# routev3_3.net
KiCad netlist of a schematic drawn in EAGLE
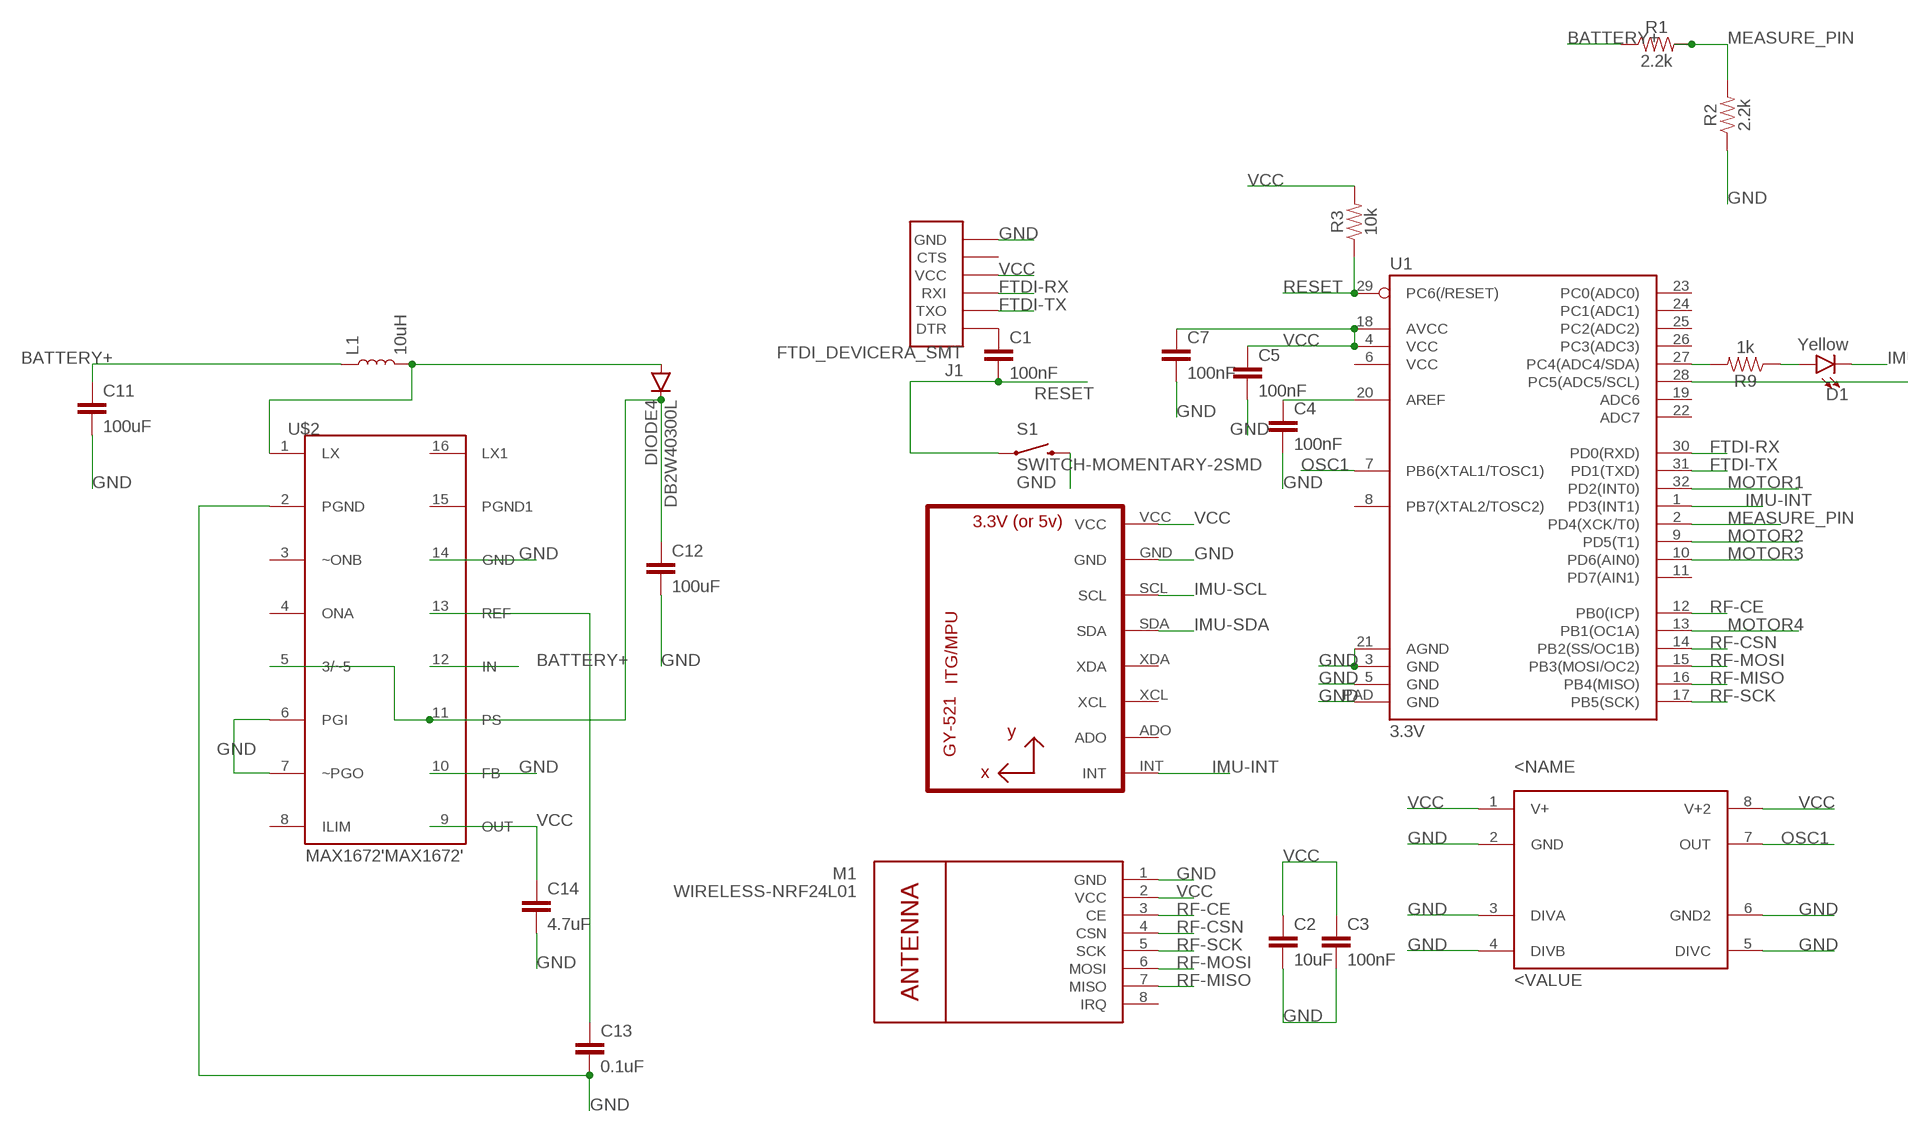
[diagram p0: schematic, sheet 1, part 1 of 2]
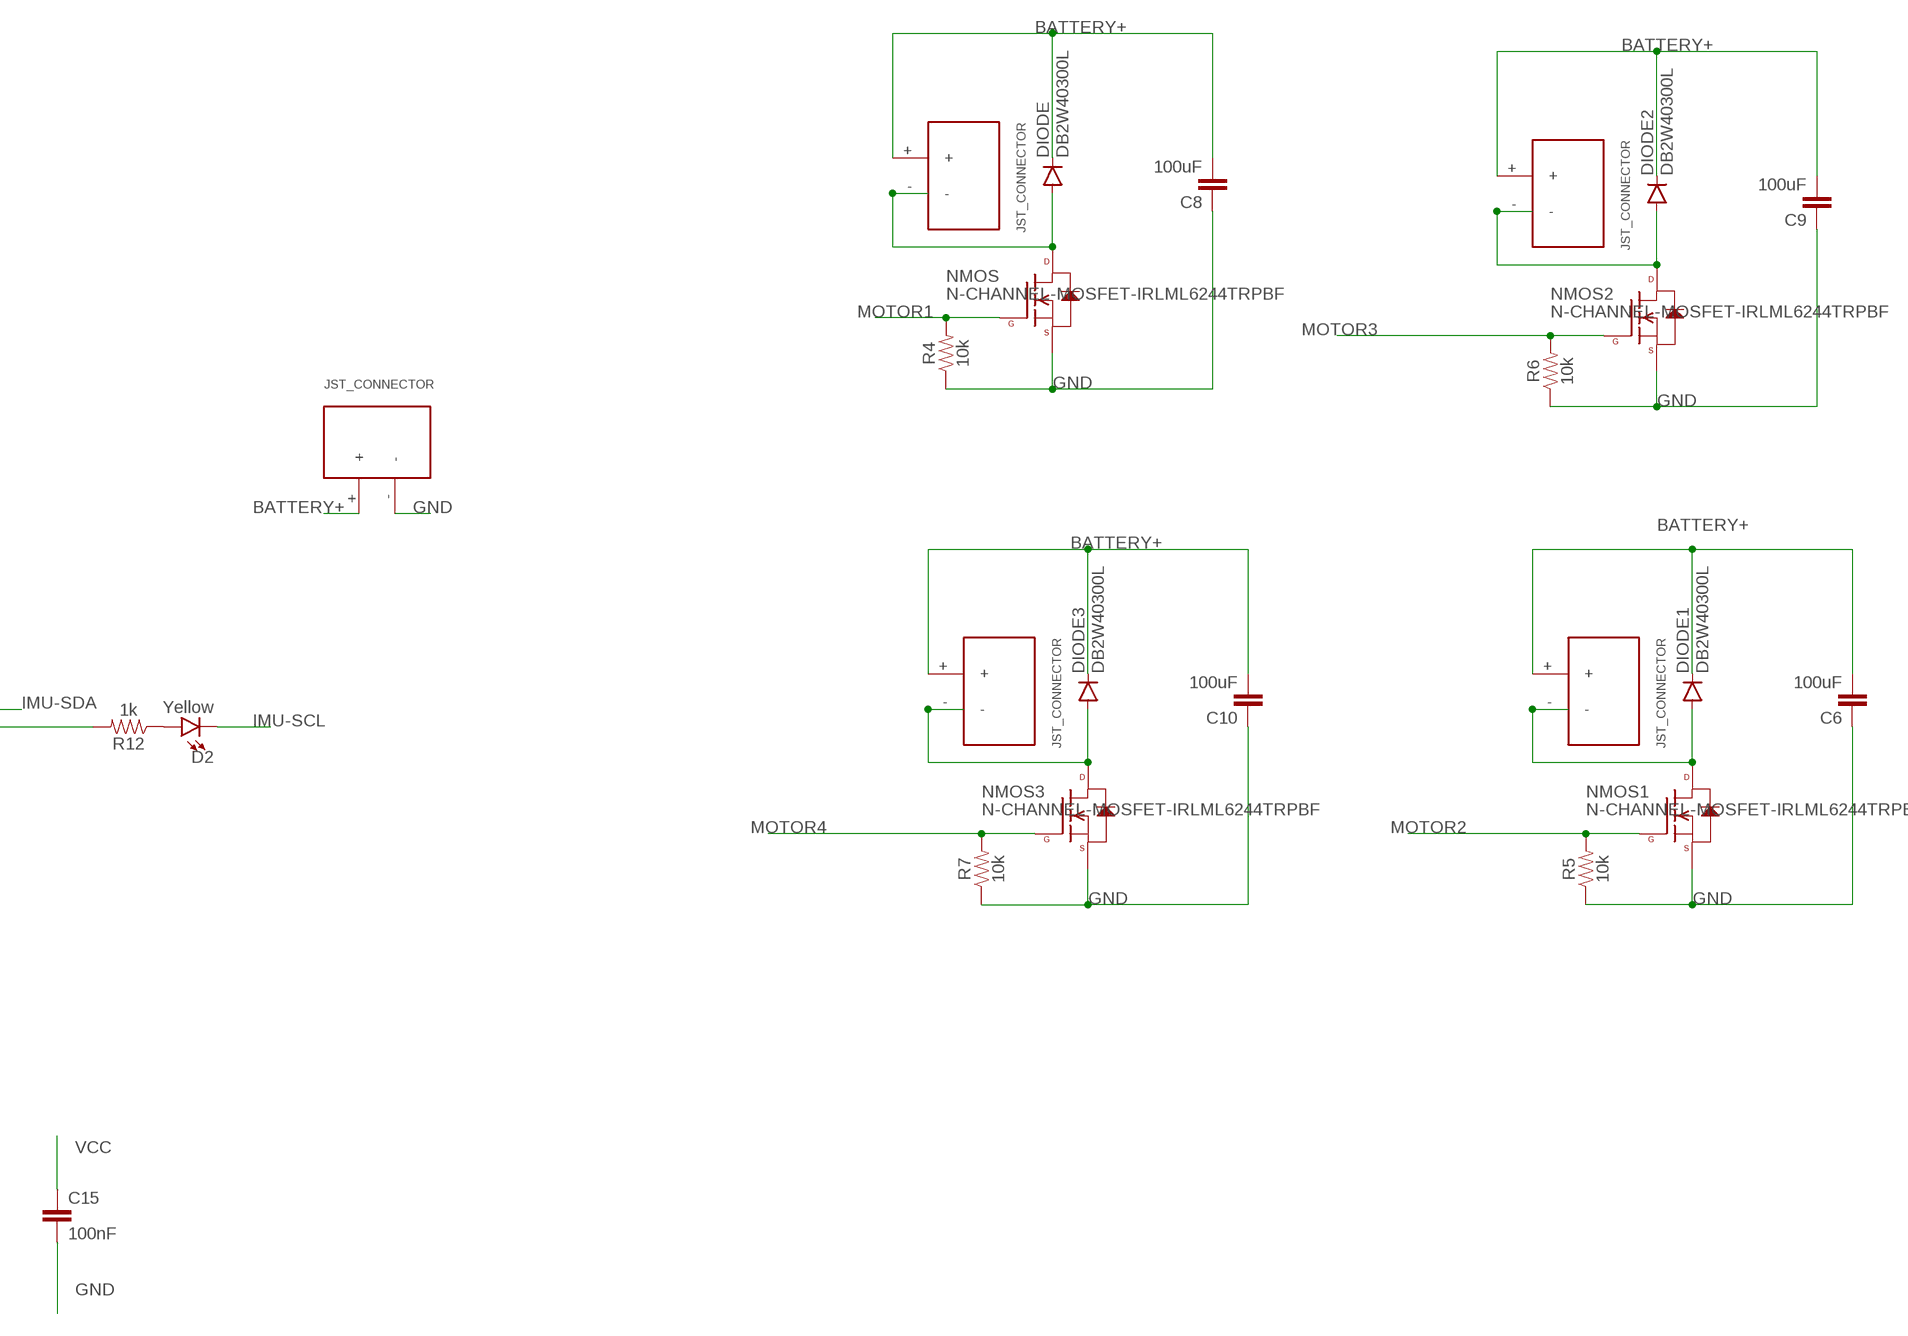
[diagram p1: schematic, sheet 1, part 2 of 2]

(export (version "E")
  (design (tool "Eeschema 10.0.6"))
  (components
    (comp (ref "C1")
      (value "100nF")
      (footprint "eagle-import:0603-CAP")
      (libsource (lib "eagle-import") (part "0.1UF-25V(+80/-20%)(0603)"))
    )
    (comp (ref "C2")
      (value "10uF")
      (footprint "eagle-import:0603-CAP")
      (libsource (lib "eagle-import") (part "CAP0603-CAP"))
    )
    (comp (ref "C3")
      (value "100nF")
      (footprint "eagle-import:0603-CAP")
      (libsource (lib "eagle-import") (part "CAP0603-CAP"))
    )
    (comp (ref "C4")
      (value "100nF")
      (footprint "eagle-import:0603-CAP")
      (libsource (lib "eagle-import") (part "CAP0603-CAP"))
    )
    (comp (ref "C5")
      (value "100nF")
      (footprint "eagle-import:0603-CAP")
      (libsource (lib "eagle-import") (part "CAP0603-CAP"))
    )
    (comp (ref "C6")
      (value "100uF")
      (footprint "eagle-import:0603-CAP")
      (libsource (lib "eagle-import") (part "CAP0603-CAP"))
    )
    (comp (ref "C7")
      (value "100nF")
      (footprint "eagle-import:0603-CAP")
      (libsource (lib "eagle-import") (part "CAP0603-CAP"))
    )
    (comp (ref "C8")
      (value "100uF")
      (footprint "eagle-import:0603-CAP")
      (libsource (lib "eagle-import") (part "CAP0603-CAP"))
    )
    (comp (ref "C9")
      (value "100uF")
      (footprint "eagle-import:0603-CAP")
      (libsource (lib "eagle-import") (part "CAP0603-CAP"))
    )
    (comp (ref "C10")
      (value "100uF")
      (footprint "eagle-import:0603-CAP")
      (libsource (lib "eagle-import") (part "CAP0603-CAP"))
    )
    (comp (ref "C11")
      (value "100uF")
      (footprint "eagle-import:0603-CAP")
      (libsource (lib "eagle-import") (part "CAP0603-CAP"))
    )
    (comp (ref "C12")
      (value "100uF")
      (footprint "eagle-import:0603-CAP")
      (libsource (lib "eagle-import") (part "CAP0603-CAP"))
    )
    (comp (ref "C13")
      (value "0.1uF")
      (footprint "eagle-import:0603-CAP")
      (libsource (lib "eagle-import") (part "CAP0603-CAP"))
    )
    (comp (ref "C14")
      (value "4.7uF")
      (footprint "eagle-import:0603-CAP")
      (libsource (lib "eagle-import") (part "CAP0603-CAP"))
    )
    (comp (ref "C15")
      (value "100nF")
      (footprint "eagle-import:0603-CAP")
      (libsource (lib "eagle-import") (part "0.1UF-25V(+80/-20%)(0603)"))
    )
    (comp (ref "D1")
      (value "Yellow")
      (footprint "eagle-import:LED-1206")
      (libsource (lib "eagle-import") (part "LED-YELLOWLILYPAD"))
    )
    (comp (ref "D2")
      (value "Yellow")
      (footprint "eagle-import:LED-1206")
      (libsource (lib "eagle-import") (part "LED-YELLOWLILYPAD"))
    )
    (comp (ref "DIODE")
      (value "DB2W40300L")
      (footprint "eagle-import:MINI2-F3-B")
      (libsource (lib "eagle-import") (part "DB2W40300L"))
    )
    (comp (ref "DIODE1")
      (value "DB2W40300L")
      (footprint "eagle-import:MINI2-F3-B")
      (libsource (lib "eagle-import") (part "DB2W40300L"))
    )
    (comp (ref "DIODE2")
      (value "DB2W40300L")
      (footprint "eagle-import:MINI2-F3-B")
      (libsource (lib "eagle-import") (part "DB2W40300L"))
    )
    (comp (ref "DIODE3")
      (value "DB2W40300L")
      (footprint "eagle-import:MINI2-F3-B")
      (libsource (lib "eagle-import") (part "DB2W40300L"))
    )
    (comp (ref "DIODE4")
      (value "DB2W40300L")
      (footprint "eagle-import:MINI2-F3-B")
      (libsource (lib "eagle-import") (part "DB2W40300L"))
    )
    (comp (ref "J1")
      (value "FTDI_DEVICERA_SMT")
      (footprint "eagle-import:FTDI_DEVICE_RA_SMT")
      (libsource (lib "eagle-import") (part "FTDI_DEVICERA_SMT"))
    )
    (comp (ref "L1")
      (value "10uH")
      (footprint "eagle-import:0603")
      (libsource (lib "eagle-import") (part "INDUCTOR-0603-33NH"))
    )
    (comp (ref "M1")
      (value "WIRELESS-NRF24L01")
      (footprint "eagle-import:WIRELESS-NRF24L01")
      (libsource (lib "eagle-import") (part "WIRELESS-NRF24L01"))
    )
    (comp (ref "MOTOR")
      (value "JST_CONNECTOR_FEMALE")
      (footprint "eagle-import:JST_CONNECTOR_FEMALE")
      (libsource (lib "eagle-import") (part "JST_CONNECTOR_FEMALE"))
    )
    (comp (ref "MOTOR1")
      (value "JST_CONNECTOR_FEMALE")
      (footprint "eagle-import:JST_CONNECTOR_FEMALE")
      (libsource (lib "eagle-import") (part "JST_CONNECTOR_FEMALE"))
    )
    (comp (ref "MOTOR2")
      (value "JST_CONNECTOR_FEMALE")
      (footprint "eagle-import:JST_CONNECTOR_FEMALE")
      (libsource (lib "eagle-import") (part "JST_CONNECTOR_FEMALE"))
    )
    (comp (ref "MOTOR3")
      (value "JST_CONNECTOR_FEMALE")
      (footprint "eagle-import:JST_CONNECTOR_FEMALE")
      (libsource (lib "eagle-import") (part "JST_CONNECTOR_FEMALE"))
    )
    (comp (ref "NMOS")
      (value "N-CHANNEL-MOSFET-IRLML6244TRPBF")
      (footprint "eagle-import:SOT23-3")
      (libsource (lib "eagle-import") (part "N-CHANNEL-MOSFET-IRLML6244TRPBF"))
    )
    (comp (ref "NMOS1")
      (value "N-CHANNEL-MOSFET-IRLML6244TRPBF")
      (footprint "eagle-import:SOT23-3")
      (libsource (lib "eagle-import") (part "N-CHANNEL-MOSFET-IRLML6244TRPBF"))
    )
    (comp (ref "NMOS2")
      (value "N-CHANNEL-MOSFET-IRLML6244TRPBF")
      (footprint "eagle-import:SOT23-3")
      (libsource (lib "eagle-import") (part "N-CHANNEL-MOSFET-IRLML6244TRPBF"))
    )
    (comp (ref "NMOS3")
      (value "N-CHANNEL-MOSFET-IRLML6244TRPBF")
      (footprint "eagle-import:SOT23-3")
      (libsource (lib "eagle-import") (part "N-CHANNEL-MOSFET-IRLML6244TRPBF"))
    )
    (comp (ref "R1")
      (value "2.2k")
      (footprint "eagle-import:0603")
      (libsource (lib "eagle-import") (part "2.2KOHM-0603-1/10W-1%"))
    )
    (comp (ref "R2")
      (value "2.2k")
      (footprint "eagle-import:0603")
      (libsource (lib "eagle-import") (part "2.2KOHM-0603-1/10W-1%"))
    )
    (comp (ref "R3")
      (value "10k")
      (footprint "eagle-import:0603")
      (libsource (lib "eagle-import") (part "2.2KOHM-0603-1/10W-1%"))
    )
    (comp (ref "R4")
      (value "10k")
      (footprint "eagle-import:0603")
      (libsource (lib "eagle-import") (part "2.2KOHM-0603-1/10W-1%"))
    )
    (comp (ref "R5")
      (value "10k")
      (footprint "eagle-import:0603")
      (libsource (lib "eagle-import") (part "2.2KOHM-0603-1/10W-1%"))
    )
    (comp (ref "R6")
      (value "10k")
      (footprint "eagle-import:0603")
      (libsource (lib "eagle-import") (part "2.2KOHM-0603-1/10W-1%"))
    )
    (comp (ref "R7")
      (value "10k")
      (footprint "eagle-import:0603")
      (libsource (lib "eagle-import") (part "2.2KOHM-0603-1/10W-1%"))
    )
    (comp (ref "R9")
      (value "1k")
      (footprint "eagle-import:0603")
      (libsource (lib "eagle-import") (part "2.2KOHM-0603-1/10W-1%"))
    )
    (comp (ref "R12")
      (value "1k")
      (footprint "eagle-import:0603")
      (libsource (lib "eagle-import") (part "2.2KOHM-0603-1/10W-1%"))
    )
    (comp (ref "S1")
      (value "SWITCH-MOMENTARY-2SMD")
      (footprint "eagle-import:TACTILE-SWITCH-SMD")
      (libsource (lib "eagle-import") (part "SWITCH-MOMENTARY-2SMD"))
    )
    (comp (ref "U$1")
      (value "JST_CONNECTOR_FEMALE")
      (footprint "eagle-import:JST_CONNECTOR_FEMALE")
      (libsource (lib "eagle-import") (part "JST_CONNECTOR_FEMALE"))
    )
    (comp (ref "U$2")
      (value "MAX1672'MAX1672'")
      (footprint "eagle-import:21-0055H_16")
      (libsource (lib "eagle-import") (part "MAX1672'MAX1672'"))
    )
    (comp (ref "U$3")
      (value "LTC6930CMS8-8.19LTC6930CMS8-8.19")
      (footprint "eagle-import:SOP65P490X110-8N")
      (libsource (lib "eagle-import") (part "LTC6930CMS8-8.19LTC6930CMS8-8.19"))
    )
    (comp (ref "U1")
      (value "3.3V")
      (footprint "eagle-import:MLF32-PAD")
      (libsource (lib "eagle-import") (part "ATMEGA328P_MLFMLF32"))
    )
    (comp (ref "U2")
      (value "GY-521MPU6050")
      (footprint "eagle-import:GY-521")
      (libsource (lib "eagle-import") (part "GY-521MPU6050"))
    )
  )
  (nets
    (net (code "1") (name "BATTERY+") (class "Default")
      (node (ref "C10") (pin "2") (pinfunction "2_2") (pintype "passive"))
      (node (ref "C11") (pin "1") (pinfunction "1_1") (pintype "passive"))
      (node (ref "C6") (pin "2") (pinfunction "2_2") (pintype "passive"))
      (node (ref "C8") (pin "2") (pinfunction "2_2") (pintype "passive"))
      (node (ref "C9") (pin "2") (pinfunction "2_2") (pintype "passive"))
      (node (ref "DIODE") (pin "NEG") (pinfunction "GPIN_NEG") (pintype "passive"))
      (node (ref "DIODE1") (pin "NEG") (pinfunction "GPIN_NEG") (pintype "passive"))
      (node (ref "DIODE2") (pin "NEG") (pinfunction "GPIN_NEG") (pintype "passive"))
      (node (ref "DIODE3") (pin "NEG") (pinfunction "GPIN_NEG") (pintype "passive"))
      (node (ref "L1") (pin "1") (pinfunction "1_1") (pintype "passive"))
      (node (ref "MOTOR") (pin "+") (pinfunction "+_+") (pintype "bidirectional"))
      (node (ref "MOTOR1") (pin "+") (pinfunction "+_+") (pintype "bidirectional"))
      (node (ref "MOTOR2") (pin "+") (pinfunction "+_+") (pintype "bidirectional"))
      (node (ref "MOTOR3") (pin "+") (pinfunction "+_+") (pintype "bidirectional"))
      (node (ref "R1") (pin "1") (pinfunction "1_1") (pintype "passive"))
      (node (ref "U$1") (pin "+") (pinfunction "+_+") (pintype "bidirectional"))
      (node (ref "U$2") (pin "12") (pinfunction "IN_12") (pintype "bidirectional"))
    )
    (net (code "2") (name "FTDI-RX") (class "Default")
      (node (ref "J1") (pin "3") (pinfunction "RXI_3") (pintype "bidirectional"))
      (node (ref "U1") (pin "30") (pinfunction "PD0(RXD)_30") (pintype "bidirectional"))
    )
    (net (code "3") (name "FTDI-TX") (class "Default")
      (node (ref "J1") (pin "2") (pinfunction "TXO_2") (pintype "bidirectional"))
      (node (ref "U1") (pin "31") (pinfunction "PD1(TXD)_31") (pintype "bidirectional"))
    )
    (net (code "4") (name "GND") (class "Default")
      (node (ref "C10") (pin "1") (pinfunction "1_1") (pintype "passive"))
      (node (ref "C11") (pin "2") (pinfunction "2_2") (pintype "passive"))
      (node (ref "C12") (pin "2") (pinfunction "2_2") (pintype "passive"))
      (node (ref "C13") (pin "2") (pinfunction "2_2") (pintype "passive"))
      (node (ref "C14") (pin "2") (pinfunction "2_2") (pintype "passive"))
      (node (ref "C15") (pin "2") (pinfunction "2_2") (pintype "passive"))
      (node (ref "C2") (pin "2") (pinfunction "2_2") (pintype "passive"))
      (node (ref "C3") (pin "2") (pinfunction "2_2") (pintype "passive"))
      (node (ref "C4") (pin "2") (pinfunction "2_2") (pintype "passive"))
      (node (ref "C5") (pin "2") (pinfunction "2_2") (pintype "passive"))
      (node (ref "C6") (pin "1") (pinfunction "1_1") (pintype "passive"))
      (node (ref "C7") (pin "2") (pinfunction "2_2") (pintype "passive"))
      (node (ref "C8") (pin "1") (pinfunction "1_1") (pintype "passive"))
      (node (ref "C9") (pin "1") (pinfunction "1_1") (pintype "passive"))
      (node (ref "J1") (pin "6") (pinfunction "GND_6") (pintype "bidirectional"))
      (node (ref "M1") (pin "1") (pinfunction "GND_1") (pintype "power_in"))
      (node (ref "NMOS") (pin "2") (pinfunction "S_2") (pintype "passive"))
      (node (ref "NMOS1") (pin "2") (pinfunction "S_2") (pintype "passive"))
      (node (ref "NMOS2") (pin "2") (pinfunction "S_2") (pintype "passive"))
      (node (ref "NMOS3") (pin "2") (pinfunction "S_2") (pintype "passive"))
      (node (ref "R2") (pin "1") (pinfunction "1_1") (pintype "passive"))
      (node (ref "R4") (pin "1") (pinfunction "1_1") (pintype "passive"))
      (node (ref "R5") (pin "1") (pinfunction "1_1") (pintype "passive"))
      (node (ref "R6") (pin "1") (pinfunction "1_1") (pintype "passive"))
      (node (ref "R7") (pin "1") (pinfunction "1_1") (pintype "passive"))
      (node (ref "S1") (pin "3") (pinfunction "2_3") (pintype "passive"))
      (node (ref "U$1") (pin "-") (pinfunction "-_-") (pintype "bidirectional"))
      (node (ref "U$2") (pin "10") (pinfunction "FB_10") (pintype "bidirectional"))
      (node (ref "U$2") (pin "14") (pinfunction "GND_14") (pintype "bidirectional"))
      (node (ref "U$2") (pin "2") (pinfunction "PGND_2") (pintype "bidirectional"))
      (node (ref "U$2") (pin "6") (pinfunction "PGI_6") (pintype "bidirectional"))
      (node (ref "U$2") (pin "7") (pinfunction "~{PGO}_7") (pintype "bidirectional"))
      (node (ref "U$3") (pin "2") (pinfunction "GND_2") (pintype "bidirectional"))
      (node (ref "U$3") (pin "3") (pinfunction "DIVA_3") (pintype "bidirectional"))
      (node (ref "U$3") (pin "4") (pinfunction "DIVB_4") (pintype "bidirectional"))
      (node (ref "U$3") (pin "5") (pinfunction "DIVC_5") (pintype "bidirectional"))
      (node (ref "U$3") (pin "6") (pinfunction "GND2_6") (pintype "bidirectional"))
      (node (ref "U1") (pin "21") (pinfunction "AGND_21") (pintype "bidirectional"))
      (node (ref "U1") (pin "3") (pinfunction "GND_3") (pintype "bidirectional"))
      (node (ref "U1") (pin "5") (pinfunction "GND_5") (pintype "bidirectional"))
      (node (ref "U1") (pin "PAD") (pinfunction "GND_PAD") (pintype "bidirectional"))
      (node (ref "U2") (pin "GND") (pinfunction "GND_GND") (pintype "bidirectional"))
    )
    (net (code "5") (name "IMU-INT") (class "Default")
      (node (ref "U1") (pin "1") (pinfunction "PD3(INT1)_1") (pintype "bidirectional"))
      (node (ref "U2") (pin "INT") (pinfunction "INT_INT") (pintype "bidirectional"))
    )
    (net (code "6") (name "IMU-SCL") (class "Default")
      (node (ref "D2") (pin "C") (pinfunction "C_C") (pintype "passive"))
      (node (ref "U2") (pin "SCL") (pinfunction "SCL_SCL") (pintype "bidirectional"))
    )
    (net (code "7") (name "IMU-SDA") (class "Default")
      (node (ref "D1") (pin "C") (pinfunction "C_C") (pintype "passive"))
      (node (ref "U2") (pin "SDA") (pinfunction "SDA_SDA") (pintype "bidirectional"))
    )
    (net (code "8") (name "MEASURE_PIN") (class "Default")
      (node (ref "R1") (pin "2") (pinfunction "2_2") (pintype "passive"))
      (node (ref "R2") (pin "2") (pinfunction "2_2") (pintype "passive"))
      (node (ref "U1") (pin "2") (pinfunction "PD4(XCK/T0)_2") (pintype "bidirectional"))
    )
    (net (code "9") (name "MOTOR1") (class "Default")
      (node (ref "NMOS") (pin "1") (pinfunction "G_1") (pintype "passive"))
      (node (ref "R4") (pin "2") (pinfunction "2_2") (pintype "passive"))
      (node (ref "U1") (pin "32") (pinfunction "PD2(INT0)_32") (pintype "bidirectional"))
    )
    (net (code "10") (name "MOTOR2") (class "Default")
      (node (ref "NMOS1") (pin "1") (pinfunction "G_1") (pintype "passive"))
      (node (ref "R5") (pin "2") (pinfunction "2_2") (pintype "passive"))
      (node (ref "U1") (pin "9") (pinfunction "PD5(T1)_9") (pintype "bidirectional"))
    )
    (net (code "11") (name "MOTOR3") (class "Default")
      (node (ref "NMOS2") (pin "1") (pinfunction "G_1") (pintype "passive"))
      (node (ref "R6") (pin "2") (pinfunction "2_2") (pintype "passive"))
      (node (ref "U1") (pin "10") (pinfunction "PD6(AIN0)_10") (pintype "bidirectional"))
    )
    (net (code "12") (name "MOTOR4") (class "Default")
      (node (ref "NMOS3") (pin "1") (pinfunction "G_1") (pintype "passive"))
      (node (ref "R7") (pin "2") (pinfunction "2_2") (pintype "passive"))
      (node (ref "U1") (pin "13") (pinfunction "PB1(OC1A)_13") (pintype "bidirectional"))
    )
    (net (code "13") (name "Net-(D1-PadA)") (class "Default")
      (node (ref "D1") (pin "A") (pinfunction "A_A") (pintype "passive"))
      (node (ref "R9") (pin "1") (pinfunction "1_1") (pintype "passive"))
    )
    (net (code "14") (name "Net-(D2-PadA)") (class "Default")
      (node (ref "D2") (pin "A") (pinfunction "A_A") (pintype "passive"))
      (node (ref "R12") (pin "1") (pinfunction "1_1") (pintype "passive"))
    )
    (net (code "15") (name "Net-(DIODE-PPIN)") (class "Default")
      (node (ref "DIODE") (pin "POS") (pinfunction "PPIN_POS") (pintype "passive"))
      (node (ref "MOTOR") (pin "-") (pinfunction "-_-") (pintype "bidirectional"))
      (node (ref "NMOS") (pin "3") (pinfunction "D_3") (pintype "passive"))
    )
    (net (code "16") (name "Net-(DIODE1-PPIN)") (class "Default")
      (node (ref "DIODE1") (pin "POS") (pinfunction "PPIN_POS") (pintype "passive"))
      (node (ref "MOTOR1") (pin "-") (pinfunction "-_-") (pintype "bidirectional"))
      (node (ref "NMOS1") (pin "3") (pinfunction "D_3") (pintype "passive"))
    )
    (net (code "17") (name "Net-(DIODE2-PPIN)") (class "Default")
      (node (ref "DIODE2") (pin "POS") (pinfunction "PPIN_POS") (pintype "passive"))
      (node (ref "MOTOR2") (pin "-") (pinfunction "-_-") (pintype "bidirectional"))
      (node (ref "NMOS2") (pin "3") (pinfunction "D_3") (pintype "passive"))
    )
    (net (code "18") (name "Net-(DIODE3-PPIN)") (class "Default")
      (node (ref "DIODE3") (pin "POS") (pinfunction "PPIN_POS") (pintype "passive"))
      (node (ref "MOTOR3") (pin "-") (pinfunction "-_-") (pintype "bidirectional"))
      (node (ref "NMOS3") (pin "3") (pinfunction "D_3") (pintype "passive"))
    )
    (net (code "19") (name "Net-(DIODE4-GPIN)") (class "Default")
      (node (ref "C12") (pin "1") (pinfunction "1_1") (pintype "passive"))
      (node (ref "DIODE4") (pin "NEG") (pinfunction "GPIN_NEG") (pintype "passive"))
      (node (ref "U$2") (pin "11") (pinfunction "PS_11") (pintype "bidirectional"))
      (node (ref "U$2") (pin "5") (pinfunction "3/~{5}_5") (pintype "bidirectional"))
    )
    (net (code "20") (name "Net-(DIODE4-PPIN)") (class "Default")
      (node (ref "DIODE4") (pin "POS") (pinfunction "PPIN_POS") (pintype "passive"))
      (node (ref "L1") (pin "2") (pinfunction "2_2") (pintype "passive"))
      (node (ref "U$2") (pin "1") (pinfunction "LX_1") (pintype "bidirectional"))
    )
    (net (code "21") (name "Net-(J1-DTR)") (class "Default")
      (node (ref "C1") (pin "1") (pinfunction "1_1") (pintype "passive"))
      (node (ref "J1") (pin "1") (pinfunction "DTR_1") (pintype "bidirectional"))
    )
    (net (code "22") (name "Net-(U$2-REF)") (class "Default")
      (node (ref "C13") (pin "1") (pinfunction "1_1") (pintype "passive"))
      (node (ref "U$2") (pin "13") (pinfunction "REF_13") (pintype "bidirectional"))
    )
    (net (code "23") (name "Net-(U1-AREF)") (class "Default")
      (node (ref "C4") (pin "1") (pinfunction "1_1") (pintype "passive"))
      (node (ref "U1") (pin "20") (pinfunction "AREF_20") (pintype "bidirectional"))
    )
    (net (code "24") (name "Net-(U1-PC4(ADC4{slash}SDA))") (class "Default")
      (node (ref "R9") (pin "2") (pinfunction "2_2") (pintype "passive"))
      (node (ref "U1") (pin "27") (pinfunction "PC4(ADC4/SDA)_27") (pintype "bidirectional"))
    )
    (net (code "25") (name "Net-(U1-PC5(ADC5{slash}SCL))") (class "Default")
      (node (ref "R12") (pin "2") (pinfunction "2_2") (pintype "passive"))
      (node (ref "U1") (pin "28") (pinfunction "PC5(ADC5/SCL)_28") (pintype "bidirectional"))
    )
    (net (code "26") (name "OSC1") (class "Default")
      (node (ref "U$3") (pin "7") (pinfunction "OUT_7") (pintype "bidirectional"))
      (node (ref "U1") (pin "7") (pinfunction "PB6(XTAL1/TOSC1)_7") (pintype "bidirectional"))
    )
    (net (code "27") (name "RESET") (class "Default")
      (node (ref "C1") (pin "2") (pinfunction "2_2") (pintype "passive"))
      (node (ref "R3") (pin "1") (pinfunction "1_1") (pintype "passive"))
      (node (ref "S1") (pin "1") (pinfunction "1_1") (pintype "passive"))
      (node (ref "U1") (pin "29") (pinfunction "PC6(/RESET)_29") (pintype "bidirectional"))
    )
    (net (code "28") (name "RF-CE") (class "Default")
      (node (ref "M1") (pin "3") (pinfunction "CE_3") (pintype "bidirectional"))
      (node (ref "U1") (pin "12") (pinfunction "PB0(ICP)_12") (pintype "bidirectional"))
    )
    (net (code "29") (name "RF-CSN") (class "Default")
      (node (ref "M1") (pin "4") (pinfunction "CSN_4") (pintype "bidirectional"))
      (node (ref "U1") (pin "14") (pinfunction "PB2(SS/OC1B)_14") (pintype "bidirectional"))
    )
    (net (code "30") (name "RF-MISO") (class "Default")
      (node (ref "M1") (pin "7") (pinfunction "MISO_7") (pintype "bidirectional"))
      (node (ref "U1") (pin "16") (pinfunction "PB4(MISO)_16") (pintype "bidirectional"))
    )
    (net (code "31") (name "RF-MOSI") (class "Default")
      (node (ref "M1") (pin "6") (pinfunction "MOSI_6") (pintype "bidirectional"))
      (node (ref "U1") (pin "15") (pinfunction "PB3(MOSI/OC2)_15") (pintype "bidirectional"))
    )
    (net (code "32") (name "RF-SCK") (class "Default")
      (node (ref "M1") (pin "5") (pinfunction "SCK_5") (pintype "bidirectional"))
      (node (ref "U1") (pin "17") (pinfunction "PB5(SCK)_17") (pintype "bidirectional"))
    )
    (net (code "33") (name "VCC") (class "Default")
      (node (ref "C14") (pin "1") (pinfunction "1_1") (pintype "passive"))
      (node (ref "C15") (pin "1") (pinfunction "1_1") (pintype "passive"))
      (node (ref "C2") (pin "1") (pinfunction "1_1") (pintype "passive"))
      (node (ref "C3") (pin "1") (pinfunction "1_1") (pintype "passive"))
      (node (ref "C5") (pin "1") (pinfunction "1_1") (pintype "passive"))
      (node (ref "C7") (pin "1") (pinfunction "1_1") (pintype "passive"))
      (node (ref "J1") (pin "4") (pinfunction "VCC_4") (pintype "bidirectional"))
      (node (ref "M1") (pin "2") (pinfunction "VCC_2") (pintype "power_in"))
      (node (ref "R3") (pin "2") (pinfunction "2_2") (pintype "passive"))
      (node (ref "U$2") (pin "9") (pinfunction "OUT_9") (pintype "bidirectional"))
      (node (ref "U$3") (pin "1") (pinfunction "V+_1") (pintype "bidirectional"))
      (node (ref "U$3") (pin "8") (pinfunction "V+2_8") (pintype "bidirectional"))
      (node (ref "U1") (pin "18") (pinfunction "AVCC_18") (pintype "bidirectional"))
      (node (ref "U1") (pin "4") (pinfunction "VCC_4") (pintype "bidirectional"))
      (node (ref "U2") (pin "VCC") (pinfunction "VCC_VCC") (pintype "bidirectional"))
    )
    (net (code "34") (name "unconnected-(J1-CTS-Pad5)") (class "Default")
      (node (ref "J1") (pin "5") (pinfunction "CTS_5") (pintype "bidirectional"))
    )
    (net (code "35") (name "unconnected-(M1-IRQ-Pad8)") (class "Default")
      (node (ref "M1") (pin "8") (pinfunction "IRQ_8") (pintype "bidirectional"))
    )
    (net (code "36") (name "unconnected-(U$2-ILIM-Pad8)") (class "Default")
      (node (ref "U$2") (pin "8") (pinfunction "ILIM_8") (pintype "bidirectional"))
    )
    (net (code "37") (name "unconnected-(U$2-LX1-Pad16)") (class "Default")
      (node (ref "U$2") (pin "16") (pinfunction "LX1_16") (pintype "bidirectional"))
    )
    (net (code "38") (name "unconnected-(U$2-ONA-Pad4)") (class "Default")
      (node (ref "U$2") (pin "4") (pinfunction "ONA_4") (pintype "bidirectional"))
    )
    (net (code "39") (name "unconnected-(U$2-PGND1-Pad15)") (class "Default")
      (node (ref "U$2") (pin "15") (pinfunction "PGND1_15") (pintype "bidirectional"))
    )
    (net (code "40") (name "unconnected-(U$2-~{ONB}-Pad3)") (class "Default")
      (node (ref "U$2") (pin "3") (pinfunction "~{ONB}_3") (pintype "bidirectional"))
    )
    (net (code "41") (name "unconnected-(U1-ADC6-Pad19)") (class "Default")
      (node (ref "U1") (pin "19") (pinfunction "ADC6_19") (pintype "bidirectional"))
    )
    (net (code "42") (name "unconnected-(U1-ADC7-Pad22)") (class "Default")
      (node (ref "U1") (pin "22") (pinfunction "ADC7_22") (pintype "bidirectional"))
    )
    (net (code "43") (name "unconnected-(U1-PB7(XTAL2{slash}TOSC2)-Pad8)") (class "Default")
      (node (ref "U1") (pin "8") (pinfunction "PB7(XTAL2/TOSC2)_8") (pintype "bidirectional"))
    )
    (net (code "44") (name "unconnected-(U1-PC0(ADC0)-Pad23)") (class "Default")
      (node (ref "U1") (pin "23") (pinfunction "PC0(ADC0)_23") (pintype "bidirectional"))
    )
    (net (code "45") (name "unconnected-(U1-PC1(ADC1)-Pad24)") (class "Default")
      (node (ref "U1") (pin "24") (pinfunction "PC1(ADC1)_24") (pintype "bidirectional"))
    )
    (net (code "46") (name "unconnected-(U1-PC2(ADC2)-Pad25)") (class "Default")
      (node (ref "U1") (pin "25") (pinfunction "PC2(ADC2)_25") (pintype "bidirectional"))
    )
    (net (code "47") (name "unconnected-(U1-PC3(ADC3)-Pad26)") (class "Default")
      (node (ref "U1") (pin "26") (pinfunction "PC3(ADC3)_26") (pintype "bidirectional"))
    )
    (net (code "48") (name "unconnected-(U1-PD7(AIN1)-Pad11)") (class "Default")
      (node (ref "U1") (pin "11") (pinfunction "PD7(AIN1)_11") (pintype "bidirectional"))
    )
    (net (code "49") (name "unconnected-(U1-VCC-Pad6)") (class "Default")
      (node (ref "U1") (pin "6") (pinfunction "VCC_6") (pintype "bidirectional"))
    )
    (net (code "50") (name "unconnected-(U2-PadADO)") (class "Default")
      (node (ref "U2") (pin "ADO") (pinfunction "ADO_ADO") (pintype "bidirectional"))
    )
    (net (code "51") (name "unconnected-(U2-PadXCL)") (class "Default")
      (node (ref "U2") (pin "XCL") (pinfunction "XCL_XCL") (pintype "bidirectional"))
    )
    (net (code "52") (name "unconnected-(U2-PadXDA)") (class "Default")
      (node (ref "U2") (pin "XDA") (pinfunction "XDA_XDA") (pintype "bidirectional"))
    )
  )
)
